# Active_Electrode.net
KiCad netlist of a schematic drawn in EAGLE
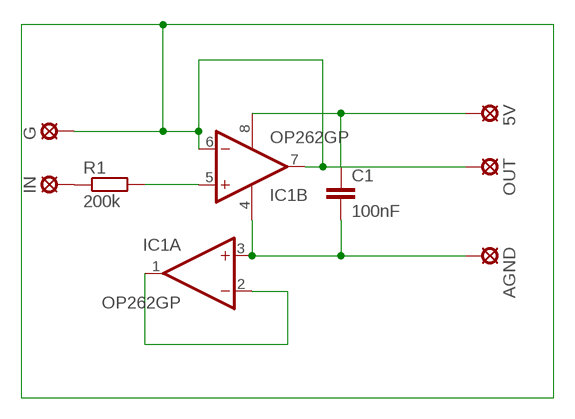
[diagram p0: schematic, sheet 1]

(export (version "E")
  (design (tool "Eeschema 10.0.6"))
  (components
    (comp (ref "5V")
      (value "LSP10")
      (footprint "eagle-import:LSP10")
      (libsource (lib "eagle-import") (part "LSP10"))
    )
    (comp (ref "AGND")
      (value "LSP10")
      (footprint "eagle-import:LSP10")
      (libsource (lib "eagle-import") (part "LSP10"))
    )
    (comp (ref "C1")
      (value "100nF")
      (footprint "eagle-import:C025-024X044")
      (libsource (lib "eagle-import") (part "C-EU025-024X044"))
    )
    (comp (ref "G")
      (value "LSP10")
      (footprint "eagle-import:LSP10")
      (libsource (lib "eagle-import") (part "LSP10"))
    )
    (comp (ref "IC1")
      (value "OP262GP")
      (footprint "eagle-import:DIL08")
      (libsource (lib "eagle-import") (part "OP262GP"))
    )
    (comp (ref "IN")
      (value "LSP10")
      (footprint "eagle-import:LSP10")
      (libsource (lib "eagle-import") (part "LSP10"))
    )
    (comp (ref "OUT")
      (value "LSP10")
      (footprint "eagle-import:LSP10")
      (libsource (lib "eagle-import") (part "LSP10"))
    )
    (comp (ref "R1")
      (value "200k")
      (footprint "eagle-import:0204_5")
      (libsource (lib "eagle-import") (part "R-EU_0204/5"))
    )
  )
  (nets
    (net (code "1") (name "Net-(IC1A-+IN)") (class "Default")
      (node (ref "AGND") (pin "MP") (pinfunction "MP_MP") (pintype "passive"))
      (node (ref "C1") (pin "2") (pinfunction "2_2") (pintype "passive"))
      (node (ref "IC1") (pin "3") (pinfunction "+IN_3") (pintype "input"))
      (node (ref "IC1") (pin "4") (pinfunction "V-_4") (pintype "power_in"))
    )
    (net (code "2") (name "Net-(IC1A--IN)") (class "Default")
      (node (ref "IC1") (pin "1") (pinfunction "OUT_1") (pintype "output"))
      (node (ref "IC1") (pin "2") (pinfunction "-IN_2") (pintype "input"))
    )
    (net (code "3") (name "Net-(IC1B-+IN)") (class "Default")
      (node (ref "IC1") (pin "5") (pinfunction "+IN_5") (pintype "input"))
      (node (ref "R1") (pin "2") (pinfunction "2_2") (pintype "passive"))
    )
    (net (code "4") (name "Net-(IC1B--IN)") (class "Default")
      (node (ref "G") (pin "MP") (pinfunction "MP_MP") (pintype "passive"))
      (node (ref "IC1") (pin "6") (pinfunction "-IN_6") (pintype "input"))
      (node (ref "IC1") (pin "7") (pinfunction "OUT_7") (pintype "output"))
      (node (ref "OUT") (pin "MP") (pinfunction "MP_MP") (pintype "passive"))
    )
    (net (code "5") (name "Net-(IC1C-V+)") (class "Default")
      (node (ref "5V") (pin "MP") (pinfunction "MP_MP") (pintype "passive"))
      (node (ref "C1") (pin "1") (pinfunction "1_1") (pintype "passive"))
      (node (ref "IC1") (pin "8") (pinfunction "V+_8") (pintype "power_in"))
    )
    (net (code "6") (name "Net-(IN-PadMP)") (class "Default")
      (node (ref "IN") (pin "MP") (pinfunction "MP_MP") (pintype "passive"))
      (node (ref "R1") (pin "1") (pinfunction "1_1") (pintype "passive"))
    )
  )
)
